# EPF-100_Logic.net
KiCad netlist of a schematic drawn in Altium Designer
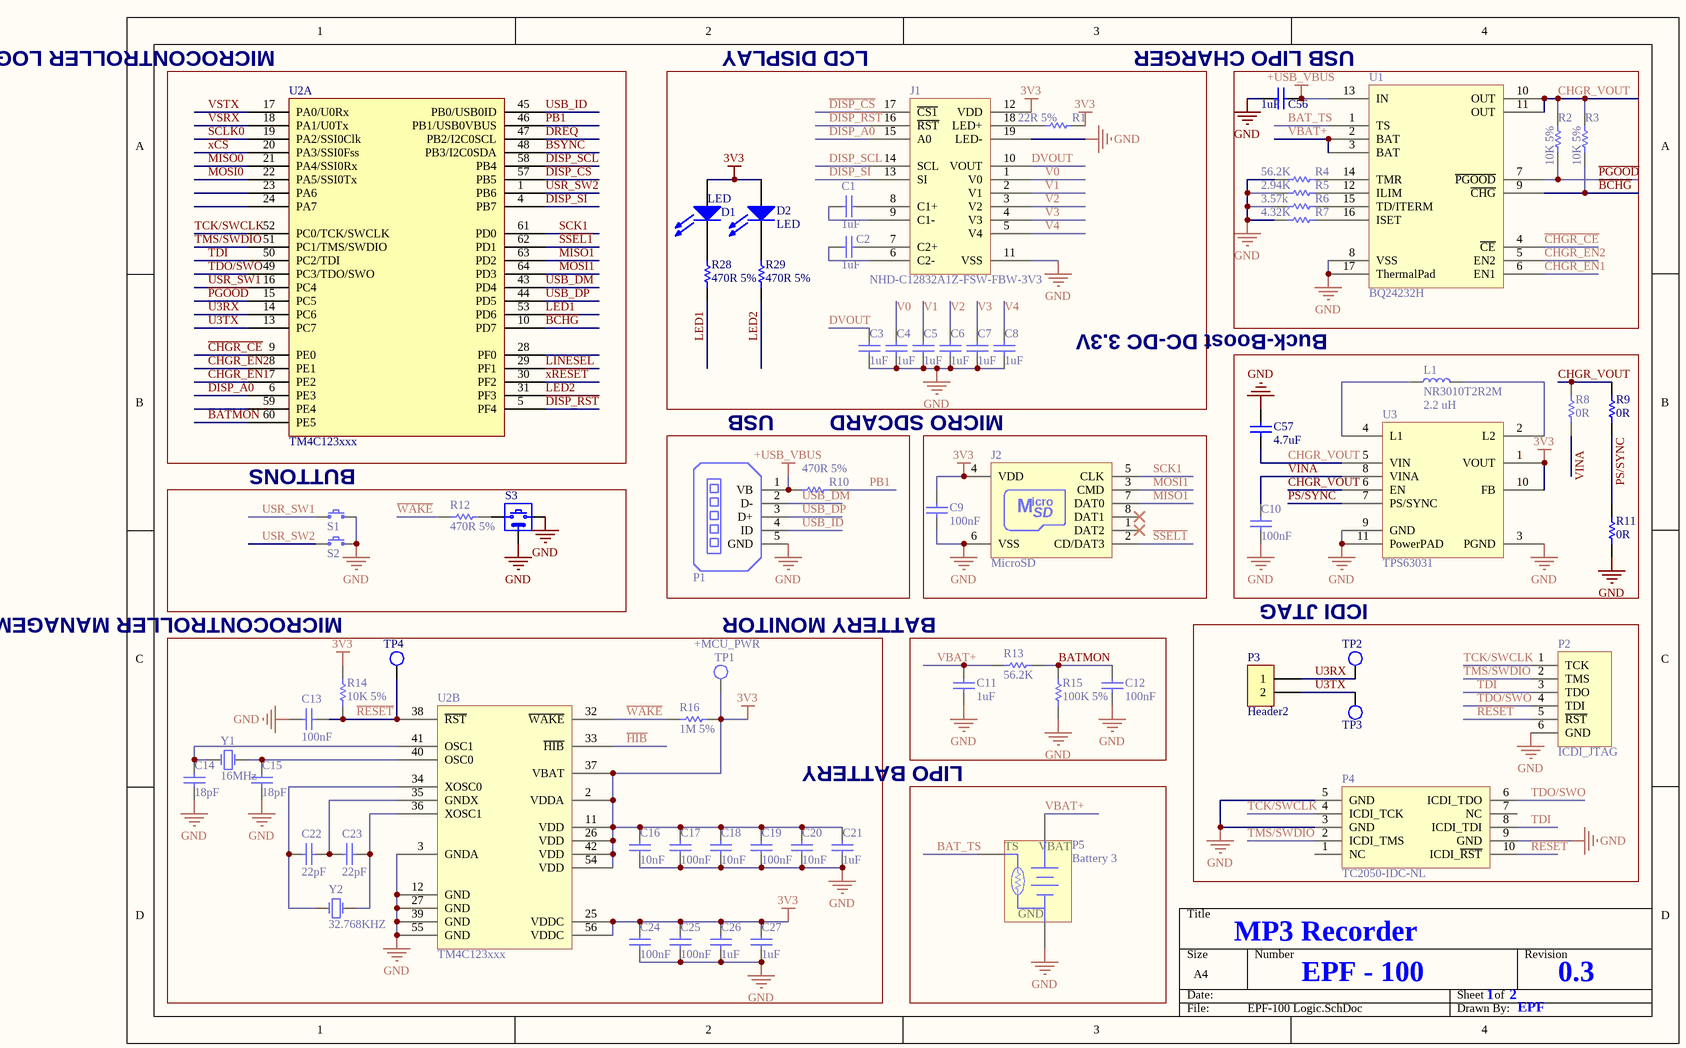
[diagram p0: EPF-100 Logic.SchDoc]

(export (version "E")
  (design (tool "Eeschema 10.0.6"))
  (components
    (comp (ref "C1")
      (value "1uF")
      (footprint "CAP0603")
      (description "X7R Ceramic Capacitors - SMD 0603")
      (fields (field (name "TOLERANCE") "X7R") (field (name "MANUFACTURER") "TDK"))
      (libsource (lib "Glober_Library") (part "CAP 1uF"))
    )
    (comp (ref "C2")
      (value "1uF")
      (footprint "CAP0603")
      (description "X7R Ceramic Capacitors - SMD 0603")
      (fields (field (name "TOLERANCE") "X7R") (field (name "MANUFACTURER") "TDK"))
      (libsource (lib "Glober_Library") (part "CAP 1uF"))
    )
    (comp (ref "C3")
      (value "1uF")
      (footprint "CAP0603")
      (description "X7R Ceramic Capacitors - SMD 0603")
      (fields (field (name "TOLERANCE") "X7R") (field (name "MANUFACTURER") "TDK"))
      (libsource (lib "Glober_Library") (part "CAP 1uF"))
    )
    (comp (ref "C4")
      (value "1uF")
      (footprint "CAP0603")
      (description "X7R Ceramic Capacitors - SMD 0603")
      (fields (field (name "TOLERANCE") "X7R") (field (name "MANUFACTURER") "TDK"))
      (libsource (lib "Glober_Library") (part "CAP 1uF"))
    )
    (comp (ref "C5")
      (value "1uF")
      (footprint "CAP0603")
      (description "X7R Ceramic Capacitors - SMD 0603")
      (fields (field (name "TOLERANCE") "X7R") (field (name "MANUFACTURER") "TDK"))
      (libsource (lib "Glober_Library") (part "CAP 1uF"))
    )
    (comp (ref "C6")
      (value "1uF")
      (footprint "CAP0603")
      (description "X7R Ceramic Capacitors - SMD 0603")
      (fields (field (name "TOLERANCE") "X7R") (field (name "MANUFACTURER") "TDK"))
      (libsource (lib "Glober_Library") (part "CAP 1uF"))
    )
    (comp (ref "C7")
      (value "1uF")
      (footprint "CAP0603")
      (description "X7R Ceramic Capacitors - SMD 0603")
      (fields (field (name "TOLERANCE") "X7R") (field (name "MANUFACTURER") "TDK"))
      (libsource (lib "Glober_Library") (part "CAP 1uF"))
    )
    (comp (ref "C8")
      (value "1uF")
      (footprint "CAP0603")
      (description "X7R Ceramic Capacitors - SMD 0603")
      (fields (field (name "TOLERANCE") "X7R") (field (name "MANUFACTURER") "TDK"))
      (libsource (lib "Glober_Library") (part "CAP 1uF"))
    )
    (comp (ref "C9")
      (value "100nF")
      (footprint "CAP0603")
      (description "X7R Ceramic Capacitors - SMD 0603")
      (fields (field (name "TOLERANCE") "X7R") (field (name "MANUFACTURER") "TDK"))
      (libsource (lib "GloberSchlib") (part "CAP 100nF"))
    )
    (comp (ref "C10")
      (value "100nF")
      (footprint "CAP0603")
      (description "X7R Ceramic Capacitors - SMD 0603")
      (fields (field (name "TOLERANCE") "X7R") (field (name "MANUFACTURER") "TDK"))
      (libsource (lib "Glober_Library") (part "CAP 100nF"))
    )
    (comp (ref "C11")
      (value "1uF")
      (footprint "CAP0603")
      (description "X7R Ceramic Capacitors - SMD 0603")
      (fields (field (name "TOLERANCE") "X7R") (field (name "MANUFACTURER") "TDK"))
      (libsource (lib "Glober_Library") (part "CAP 1uF"))
    )
    (comp (ref "C12")
      (value "100nF")
      (footprint "CAP0603")
      (description "X7R Ceramic Capacitors - SMD 0603")
      (fields (field (name "TOLERANCE") "X7R") (field (name "MANUFACTURER") "TDK"))
      (libsource (lib "Glober_Library") (part "CAP 100nF"))
    )
    (comp (ref "C13")
      (value "100nF")
      (footprint "CAP0603")
      (description "X7R Ceramic Capacitors - SMD 0603")
      (fields (field (name "TOLERANCE") "X7R") (field (name "MANUFACTURER") "TDK"))
      (libsource (lib "GloberSchlib") (part "CAP 100nF"))
    )
    (comp (ref "C14")
      (value "18pF")
      (footprint "CAP0603")
      (description "C0G Ceramic Capacitors - SMD 0603")
      (fields (field (name "TOLERANCE") "C0G") (field (name "MANUFACTURER") "Murata"))
      (libsource (lib "GloberSchlib") (part "CAP 18pF"))
    )
    (comp (ref "C15")
      (value "18pF")
      (footprint "CAP0603")
      (description "C0G Ceramic Capacitors - SMD 0603")
      (fields (field (name "TOLERANCE") "C0G") (field (name "MANUFACTURER") "Murata"))
      (libsource (lib "GloberSchlib") (part "CAP 18pF"))
    )
    (comp (ref "C16")
      (value "10nF")
      (footprint "CAP0603")
      (description "X7R Ceramic Capacitors - SMD 0603")
      (fields (field (name "TOLERANCE") "X7R") (field (name "MANUFACTURER") "TDK"))
      (libsource (lib "GloberSchlib") (part "CAP 10nF"))
    )
    (comp (ref "C17")
      (value "100nF")
      (footprint "CAP0603")
      (description "X7R Ceramic Capacitors - SMD 0603")
      (fields (field (name "TOLERANCE") "X7R") (field (name "MANUFACTURER") "TDK"))
      (libsource (lib "GloberSchlib") (part "CAP 100nF"))
    )
    (comp (ref "C18")
      (value "10nF")
      (footprint "CAP0603")
      (description "X7R Ceramic Capacitors - SMD 0603")
      (fields (field (name "TOLERANCE") "X7R") (field (name "MANUFACTURER") "TDK"))
      (libsource (lib "GloberSchlib") (part "CAP 10nF"))
    )
    (comp (ref "C19")
      (value "100nF")
      (footprint "CAP0603")
      (description "X7R Ceramic Capacitors - SMD 0603")
      (fields (field (name "TOLERANCE") "X7R") (field (name "MANUFACTURER") "TDK"))
      (libsource (lib "GloberSchlib") (part "CAP 100nF"))
    )
    (comp (ref "C20")
      (value "10nF")
      (footprint "CAP0603")
      (description "X7R Ceramic Capacitors - SMD 0603")
      (fields (field (name "TOLERANCE") "X7R") (field (name "MANUFACTURER") "TDK"))
      (libsource (lib "GloberSchlib") (part "CAP 10nF"))
    )
    (comp (ref "C21")
      (value "1uF")
      (footprint "CAP0603")
      (description "X7R Ceramic Capacitors - SMD 0603")
      (fields (field (name "TOLERANCE") "X7R") (field (name "MANUFACTURER") "TDK"))
      (libsource (lib "GloberSchlib") (part "CAP 1uF"))
    )
    (comp (ref "C22")
      (value "22pF")
      (footprint "CAP0603")
      (description "C0G Ceramic Capacitors - SMD 0603")
      (fields (field (name "TOLERANCE") "C0G") (field (name "MANUFACTURER") "TDK"))
      (libsource (lib "GloberSchlib") (part "CAP 22pF"))
    )
    (comp (ref "C23")
      (value "22pF")
      (footprint "CAP0603")
      (description "C0G Ceramic Capacitors - SMD 0603")
      (fields (field (name "TOLERANCE") "C0G") (field (name "MANUFACTURER") "TDK"))
      (libsource (lib "GloberSchlib") (part "CAP 22pF"))
    )
    (comp (ref "C24")
      (value "100nF")
      (footprint "CAP0603")
      (description "X7R Ceramic Capacitors - SMD 0603")
      (fields (field (name "TOLERANCE") "X7R") (field (name "MANUFACTURER") "TDK"))
      (libsource (lib "GloberSchlib") (part "CAP 100nF"))
    )
    (comp (ref "C25")
      (value "100nF")
      (footprint "CAP0603")
      (description "X7R Ceramic Capacitors - SMD 0603")
      (fields (field (name "TOLERANCE") "X7R") (field (name "MANUFACTURER") "TDK"))
      (libsource (lib "GloberSchlib") (part "CAP 100nF"))
    )
    (comp (ref "C26")
      (value "1uF")
      (footprint "CAP0603")
      (description "X7R Ceramic Capacitors - SMD 0603")
      (fields (field (name "TOLERANCE") "X7R") (field (name "MANUFACTURER") "TDK"))
      (libsource (lib "GloberSchlib") (part "CAP 1uF"))
    )
    (comp (ref "C27")
      (value "1uF")
      (footprint "CAP0603")
      (description "X7R Ceramic Capacitors - SMD 0603")
      (fields (field (name "TOLERANCE") "X7R") (field (name "MANUFACTURER") "TDK"))
      (libsource (lib "GloberSchlib") (part "CAP 1uF"))
    )
    (comp (ref "C56")
      (value "1uF")
      (footprint "CAP0603")
      (description "X7R Ceramic Capacitors - SMD 0603")
      (fields (field (name "TOLERANCE") "X7R") (field (name "MANUFACTURER") "TDK"))
      (libsource (lib "Glober_Library") (part "CAP 1uF"))
    )
    (comp (ref "C57")
      (value "4.7uF")
      (footprint "CAP0603")
      (description "X7R Ceramic Capacitors - SMD 0603")
      (fields (field (name "TOLERANCE") "X7R") (field (name "MANUFACTURER") "Murata Electronics"))
      (libsource (lib "Glober_Library") (part "CAP 4.7uF"))
    )
    (comp (ref "D1") (value "LED") (footprint "LED0603") (libsource (lib "epf") (part "LED1")))
    (comp (ref "D2") (value "LED") (footprint "LED0603") (libsource (lib "epf") (part "LED1")))
    (comp (ref "J1")
      (value "NHD-C12832A1Z-FSW-FBW-3V3")
      (footprint "NHD-C12832A1Z")
      (description "LCD NHD-C12832A1Z-FSW-FBW-3V3")
      (libsource (lib "Glober_Library") (part "NHD-C12832A1Z-FSW-FBW-3V3"))
    )
    (comp (ref "J2")
      (value "MicroSD")
      (footprint "ALPS-SCHD1A0101")
      (description "MicroSD Memory Card Connector")
      (fields (field (name "MANUFACTURER") "ALPS"))
      (libsource (lib "GloberSchlib") (part "ALPS-SCHD1A0101"))
    )
    (comp (ref "L1")
      (value "NR3010T2R2M")
      (footprint "NR3010")
      (fields
        (field (name "MANUFACTURER") "Taiyo Yuden")
        (field (name "MOUSER PART #") "963-NR3010T2R2M")
        (field (name "ALTIUM_VALUE") "2.2 uH")
      )
      (libsource (lib "Glober_Library") (part "NR3010T2R2M"))
    )
    (comp (ref "P1")
      (value "USB extension")
      (footprint "HDR1X5 - USB")
      (libsource (lib "GloberSchlib") (part "USB"))
    )
    (comp (ref "P2")
      (value "ICDI_JTAG")
      (footprint "HDR1X6")
      (description "DEBUG ICDI_JTAG")
      (libsource (lib "Glober_Library") (part "ICDI_JTAG"))
    )
    (comp (ref "P3") (value "Header2") (footprint "Header2Macho") (libsource (lib "epf") (part "Header2")))
    (comp (ref "P4")
      (value "TC2050-IDC-NL")
      (footprint "TC2050-IDC-NL")
      (fields (field (name "MANUFACTURER") "Tag-Connect LLC"))
      (libsource (lib "GloberSchlib") (part "TC2050-IDC-NL"))
    )
    (comp (ref "P5")
      (value "Battery 3")
      (footprint "HDR1X3")
      (description "Header, 3-Pin")
      (fields (field (name "PUBLISHER") "Altium Limited"))
      (libsource (lib "GloberSchlib") (part "Battery 3"))
    )
    (comp (ref "R1")
      (value "22R 5%")
      (footprint "RES0603")
      (description "5% Thick Film Resistors - SMD 0603")
      (fields (field (name "TOLERANCE") "5%") (field (name "MANUFACTURER") "Bourns"))
      (libsource (lib "Glober_Library") (part "RES 22R"))
    )
    (comp (ref "R2")
      (value "10K 5%")
      (footprint "RES0603")
      (description "5% Thick Film Resistors - SMD 0603")
      (fields (field (name "TOLERANCE") "5%") (field (name "MANUFACTURER") "Bourns"))
      (libsource (lib "Glober_Library") (part "RES 10K"))
    )
    (comp (ref "R3")
      (value "10K 5%")
      (footprint "RES0603")
      (description "5% Thick Film Resistors - SMD 0603")
      (fields (field (name "TOLERANCE") "5%") (field (name "MANUFACTURER") "Bourns"))
      (libsource (lib "Glober_Library") (part "RES 10K"))
    )
    (comp (ref "R4")
      (value "56.2K")
      (footprint "RES0603")
      (description "1% Thick Film Resistors - SMD 0603")
      (fields (field (name "TOLERANCE") "5%") (field (name "MANUFACTURER") "Panasonic"))
      (libsource (lib "Glober_Library") (part "RES 56.2K"))
    )
    (comp (ref "R5")
      (value "2.94K")
      (footprint "RES0603")
      (description "1% Thick Film Resistors - SMD 0603")
      (fields (field (name "TOLERANCE") "1%") (field (name "MANUFACTURER") "Vishay / Dale"))
      (libsource (lib "Glober_Library") (part "RES 2.94K"))
    )
    (comp (ref "R6")
      (value "3.57k")
      (footprint "RES0603")
      (description "1% Thick Film Resistors - SMD 0603")
      (fields (field (name "TOLERANCE") "1%") (field (name "MANUFACTURER") "Panasonic"))
      (libsource (lib "Glober_Library") (part "RES 3.57k"))
    )
    (comp (ref "R7")
      (value "4.32K")
      (footprint "RES0603")
      (description "1% Thick Film Resistors - SMD 0603")
      (fields (field (name "TOLERANCE") "1%") (field (name "MANUFACTURER") "Panasonic"))
      (libsource (lib "Glober_Library") (part "RES 4.32K"))
    )
    (comp (ref "R8")
      (value "0R")
      (footprint "RES0603")
      (description "5% Thick Film Resistors - SMD 0603")
      (fields (field (name "TOLERANCE") "5%") (field (name "MANUFACTURER") "KOA Speer"))
      (libsource (lib "Glober_Library") (part "RES 0R"))
    )
    (comp (ref "R9")
      (value "0R")
      (footprint "RES0603")
      (description "5% Thick Film Resistors - SMD 0603")
      (fields (field (name "TOLERANCE") "5%") (field (name "MANUFACTURER") "KOA Speer"))
      (libsource (lib "Glober_Library") (part "RES 0R"))
    )
    (comp (ref "R10")
      (value "470R 5%")
      (footprint "RES0603")
      (description "5% Thick Film Resistors - SMD 0603")
      (fields (field (name "TOLERANCE") "5%") (field (name "MANUFACTURER") "Bourns"))
      (libsource (lib "Glober_Library") (part "RES 470R"))
    )
    (comp (ref "R11")
      (value "0R")
      (footprint "RES0603")
      (description "5% Thick Film Resistors - SMD 0603")
      (fields (field (name "TOLERANCE") "5%") (field (name "MANUFACTURER") "KOA Speer"))
      (libsource (lib "Glober_Library") (part "RES 0R"))
    )
    (comp (ref "R12")
      (value "470R 5%")
      (footprint "RES0603")
      (description "5% Thick Film Resistors - SMD 0603")
      (fields (field (name "TOLERANCE") "5%") (field (name "MANUFACTURER") "Bourns"))
      (libsource (lib "Glober_Library") (part "RES 470R"))
    )
    (comp (ref "R13")
      (value "56.2K")
      (footprint "RES0603")
      (description "1% Thick Film Resistors - SMD 0603")
      (fields (field (name "TOLERANCE") "5%") (field (name "MANUFACTURER") "Panasonic"))
      (libsource (lib "Glober_Library") (part "RES 56.2K"))
    )
    (comp (ref "R14")
      (value "10K 5%")
      (footprint "RES0603")
      (description "5% Thick Film Resistors - SMD 0603")
      (fields (field (name "TOLERANCE") "5%") (field (name "MANUFACTURER") "Bourns"))
      (libsource (lib "Glober_Library") (part "RES 10K"))
    )
    (comp (ref "R15")
      (value "100K 5%")
      (footprint "RES0603")
      (description "5% Thick Film Resistors - SMD 0603")
      (fields (field (name "TOLERANCE") "5%") (field (name "MANUFACTURER") "Bourns"))
      (libsource (lib "Glober_Library") (part "RES 100K"))
    )
    (comp (ref "R16")
      (value "1M 5%")
      (footprint "RES0603")
      (description "5% Thick Film Resistors - SMD 0603")
      (fields (field (name "TOLERANCE") "5%") (field (name "MANUFACTURER") "Bourns"))
      (libsource (lib "Glober_Library") (part "RES 1M"))
    )
    (comp (ref "R28")
      (value "470R 5%")
      (footprint "RES0603")
      (description "5% Thick Film Resistors - SMD 0603")
      (fields (field (name "TOLERANCE") "5%") (field (name "MANUFACTURER") "Bourns"))
      (libsource (lib "Glober_Library") (part "RES 470R"))
    )
    (comp (ref "R29")
      (value "470R 5%")
      (footprint "RES0603")
      (description "5% Thick Film Resistors - SMD 0603")
      (fields (field (name "TOLERANCE") "5%") (field (name "MANUFACTURER") "Bourns"))
      (libsource (lib "Glober_Library") (part "RES 470R"))
    )
    (comp (ref "S1")
      (value "switch")
      (footprint "TACTILE SWITCH 3.5x6")
      (description "TACTILE SWITCH 3.5x6")
      (libsource (lib "Glober_Library") (part "SW-PB"))
    )
    (comp (ref "S2")
      (value "switch")
      (footprint "TACTILE SWITCH 3.5x6")
      (description "TACTILE SWITCH 3.5x6")
      (libsource (lib "Glober_Library") (part "SW-PB"))
    )
    (comp (ref "S3")
      (value "switch")
      (footprint "B3U-3100P-B")
      (description "B3U-3100P-B")
      (fields (field (name "MANUFACTURER") "Omron"))
      (libsource (lib "Glober_Library") (part "B3U-3100P-B"))
    )
    (comp (ref "TP1")
      (value "+MCU_PWR")
      (footprint "PCB TEST POINT")
      (libsource (lib "Glober_Library") (part "PCB TEST POINT"))
    )
    (comp (ref "TP2")
      (value "PCB TEST POINT")
      (footprint "PCB TEST POINT")
      (libsource (lib "Glober_Library") (part "PCB TEST POINT"))
    )
    (comp (ref "TP3")
      (value "PCB TEST POINT")
      (footprint "PCB TEST POINT")
      (libsource (lib "Glober_Library") (part "PCB TEST POINT"))
    )
    (comp (ref "TP4")
      (value "PCB TEST POINT")
      (footprint "PCB TEST POINT")
      (libsource (lib "Glober_Library") (part "PCB TEST POINT"))
    )
    (comp (ref "U1")
      (value "BQ24232H")
      (footprint "QFN50P300X300-16V6N")
      (description "USB-Friendly Lithium-Ion Battery Charger and Power-Path Management IC")
      (fields (field (name "MANUFACTURER") "Ti"))
      (libsource (lib "Glober_Library") (part "BQ24232H"))
    )
    (comp (ref "U2")
      (value "TM4C123xxx")
      (footprint "LQFP64_N")
      (fields (field (name "MANUFACTURER") "Ti"))
      (libsource (lib "Glober_Library") (part "TM4C123"))
    )
    (comp (ref "U3")
      (value "TPS63031")
      (footprint "SON50P300X300X80-10W2N")
      (description "HIGH EFFICIENCY SINGLE INDUCTOR BUCK-BOOST CONVERTER WITH 1-A SWITCHES")
      (fields (field (name "MANUFACTURER") "Ti"))
      (libsource (lib "Glober_Library") (part "TPS63031"))
    )
    (comp (ref "Y1")
      (value "16MHz")
      (footprint "NX5032GA")
      (description "Crystal, 16.00 MHz 5.0x3.2mm SMT")
      (fields (field (name "MANUFACTURER") "NDK"))
      (libsource (lib "GloberSchlib") (part "XTAL 16MHz"))
    )
    (comp (ref "Y2")
      (value "32.768KHZ")
      (footprint "AB26TRB-32.768KHZ- T")
      (description "Crystal, 32.768 kHz Radial Can")
      (fields (field (name "MANUFACTURER") "Abracon"))
      (libsource (lib "GloberSchlib") (part "XTAL 32.768KHZ"))
    )
  )
  (nets
    (net (code "1") (name "+USB_VBUS") (class "Default")
      (node (ref "C56") (pin "1") (pinfunction "1_1") (pintype "passive"))
      (node (ref "P1") (pin "1") (pinfunction "VB_1") (pintype "passive"))
      (node (ref "R10") (pin "1") (pinfunction "1_1") (pintype "passive"))
      (node (ref "U1") (pin "13") (pinfunction "IN_13") (pintype "passive"))
    )
    (net (code "2") (name "/BATMON") (class "Default")
      (node (ref "C12") (pin "2") (pinfunction "2_2") (pintype "passive"))
      (node (ref "R13") (pin "2") (pinfunction "2_2") (pintype "passive"))
      (node (ref "R15") (pin "2") (pinfunction "2_2") (pintype "passive"))
      (node (ref "U2") (pin "60") (pinfunction "PE5_60") (pintype "passive"))
    )
    (net (code "3") (name "/BAT_TS") (class "Default")
      (node (ref "P5") (pin "1") (pinfunction "TS_1") (pintype "passive"))
      (node (ref "U1") (pin "1") (pinfunction "TS_1") (pintype "passive"))
    )
    (net (code "4") (name "/BSYNC") (class "Default")
      (node (ref "U2") (pin "48") (pinfunction "PB3/I2C0SDA_48") (pintype "passive"))
    )
    (net (code "5") (name "/CHGR_EN1") (class "Default")
      (node (ref "U1") (pin "6") (pinfunction "EN1_6") (pintype "passive"))
      (node (ref "U2") (pin "7") (pinfunction "PE2_7") (pintype "passive"))
    )
    (net (code "6") (name "/CHGR_EN2") (class "Default")
      (node (ref "U1") (pin "5") (pinfunction "EN2_5") (pintype "passive"))
      (node (ref "U2") (pin "8") (pinfunction "PE1_8") (pintype "passive"))
    )
    (net (code "7") (name "/CHGR_VOUT") (class "Default")
      (node (ref "C57") (pin "1") (pinfunction "1_1") (pintype "passive"))
      (node (ref "R2") (pin "2") (pinfunction "2_2") (pintype "passive"))
      (node (ref "R3") (pin "2") (pinfunction "2_2") (pintype "passive"))
      (node (ref "R8") (pin "1") (pinfunction "1_1") (pintype "passive"))
      (node (ref "R9") (pin "1") (pinfunction "1_1") (pintype "passive"))
      (node (ref "U1") (pin "10") (pinfunction "OUT_10") (pintype "passive"))
      (node (ref "U1") (pin "11") (pinfunction "OUT_11") (pintype "passive"))
      (node (ref "U3") (pin "5") (pinfunction "VIN_5") (pintype "passive"))
      (node (ref "U3") (pin "6") (pinfunction "EN_6") (pintype "passive"))
    )
    (net (code "8") (name "/DISP_A0") (class "Default")
      (node (ref "J1") (pin "15") (pinfunction "A0_15") (pintype "passive"))
      (node (ref "U2") (pin "6") (pinfunction "PE3_6") (pintype "passive"))
    )
    (net (code "9") (name "/DISP_SCL") (class "Default")
      (node (ref "J1") (pin "14") (pinfunction "SCL_14") (pintype "passive"))
      (node (ref "U2") (pin "58") (pinfunction "PB4_58") (pintype "passive"))
    )
    (net (code "10") (name "/DISP_SI") (class "Default")
      (node (ref "J1") (pin "13") (pinfunction "SI_13") (pintype "passive"))
      (node (ref "U2") (pin "4") (pinfunction "PB7_4") (pintype "passive"))
    )
    (net (code "11") (name "/DREQ") (class "Default")
      (node (ref "U2") (pin "47") (pinfunction "PB2/I2C0SCL_47") (pintype "passive"))
    )
    (net (code "12") (name "/DVOUT") (class "Default")
      (node (ref "C3") (pin "1") (pinfunction "1_1") (pintype "passive"))
      (node (ref "J1") (pin "10") (pinfunction "VOUT_10") (pintype "passive"))
    )
    (net (code "13") (name "/LED1") (class "Default")
      (node (ref "R28") (pin "1") (pinfunction "1_1") (pintype "passive"))
      (node (ref "U2") (pin "53") (pinfunction "PD6_53") (pintype "passive"))
    )
    (net (code "14") (name "/LED2") (class "Default")
      (node (ref "R29") (pin "1") (pinfunction "1_1") (pintype "passive"))
      (node (ref "U2") (pin "31") (pinfunction "PF3_31") (pintype "passive"))
    )
    (net (code "15") (name "/LINESEL") (class "Default")
      (node (ref "U2") (pin "29") (pinfunction "PF1_29") (pintype "passive"))
    )
    (net (code "16") (name "/MISO0") (class "Default")
      (node (ref "U2") (pin "21") (pinfunction "PA4/SSI0Rx_21") (pintype "passive"))
    )
    (net (code "17") (name "/MISO1") (class "Default")
      (node (ref "J2") (pin "7") (pinfunction "DAT0_7") (pintype "passive"))
      (node (ref "U2") (pin "63") (pinfunction "PD2_63") (pintype "passive"))
    )
    (net (code "18") (name "/MOSI0") (class "Default")
      (node (ref "U2") (pin "22") (pinfunction "PA5/SSI0Tx_22") (pintype "passive"))
    )
    (net (code "19") (name "/MOSI1") (class "Default")
      (node (ref "J2") (pin "3") (pinfunction "CMD_3") (pintype "passive"))
      (node (ref "U2") (pin "64") (pinfunction "PD3_64") (pintype "passive"))
    )
    (net (code "20") (name "/PB1") (class "Default")
      (node (ref "R10") (pin "2") (pinfunction "2_2") (pintype "passive"))
      (node (ref "U2") (pin "46") (pinfunction "PB1/USB0VBUS_46") (pintype "passive"))
    )
    (net (code "21") (name "/PS{slash}SYNC") (class "Default")
      (node (ref "R11") (pin "2") (pinfunction "2_2") (pintype "passive"))
      (node (ref "R9") (pin "2") (pinfunction "2_2") (pintype "passive"))
      (node (ref "U3") (pin "7") (pinfunction "PS/SYNC_7") (pintype "passive"))
    )
    (net (code "22") (name "/SCK1") (class "Default")
      (node (ref "J2") (pin "5") (pinfunction "CLK_5") (pintype "passive"))
      (node (ref "U2") (pin "61") (pinfunction "PD0_61") (pintype "passive"))
    )
    (net (code "23") (name "/SCLK0") (class "Default")
      (node (ref "U2") (pin "19") (pinfunction "PA2/SSI0Clk_19") (pintype "passive"))
    )
    (net (code "24") (name "/SSEL1") (class "Default")
      (node (ref "J2") (pin "2") (pinfunction "CD/DAT3_2") (pintype "passive"))
      (node (ref "U2") (pin "62") (pinfunction "PD1_62") (pintype "passive"))
    )
    (net (code "25") (name "/TCK{slash}SWCLK") (class "Default")
      (node (ref "P2") (pin "1") (pinfunction "TCK_1") (pintype "passive"))
      (node (ref "P4") (pin "4") (pinfunction "ICDI_TCK_4") (pintype "passive"))
      (node (ref "U2") (pin "52") (pinfunction "PC0/TCK/SWCLK_52") (pintype "passive"))
    )
    (net (code "26") (name "/TDI") (class "Default")
      (node (ref "P2") (pin "3") (pinfunction "TDO_3") (pintype "passive"))
      (node (ref "P4") (pin "8") (pinfunction "ICDI_TDI_8") (pintype "passive"))
      (node (ref "U2") (pin "50") (pinfunction "PC2/TDI_50") (pintype "passive"))
    )
    (net (code "27") (name "/TDO{slash}SWO") (class "Default")
      (node (ref "P2") (pin "4") (pinfunction "TDI_4") (pintype "passive"))
      (node (ref "P4") (pin "6") (pinfunction "ICDI_TDO_6") (pintype "passive"))
      (node (ref "U2") (pin "49") (pinfunction "PC3/TDO/SWO_49") (pintype "passive"))
    )
    (net (code "28") (name "/TMS{slash}SWDIO") (class "Default")
      (node (ref "P2") (pin "2") (pinfunction "TMS_2") (pintype "passive"))
      (node (ref "P4") (pin "2") (pinfunction "ICDI_TMS_2") (pintype "passive"))
      (node (ref "U2") (pin "51") (pinfunction "PC1/TMS/SWDIO_51") (pintype "passive"))
    )
    (net (code "29") (name "/U3RX") (class "Default")
      (node (ref "P3") (pin "1") (pinfunction "1_1") (pintype "passive"))
      (node (ref "TP2") (pin "1") (pinfunction "1_1") (pintype "passive"))
      (node (ref "U2") (pin "14") (pinfunction "PC6_14") (pintype "passive"))
    )
    (net (code "30") (name "/U3TX") (class "Default")
      (node (ref "P3") (pin "2") (pinfunction "2_2") (pintype "passive"))
      (node (ref "TP3") (pin "1") (pinfunction "1_1") (pintype "passive"))
      (node (ref "U2") (pin "13") (pinfunction "PC7_13") (pintype "passive"))
    )
    (net (code "31") (name "/USB_DM") (class "Default")
      (node (ref "P1") (pin "2") (pinfunction "D-_2") (pintype "passive"))
      (node (ref "U2") (pin "43") (pinfunction "PD4_43") (pintype "passive"))
    )
    (net (code "32") (name "/USB_DP") (class "Default")
      (node (ref "P1") (pin "3") (pinfunction "D+_3") (pintype "passive"))
      (node (ref "U2") (pin "44") (pinfunction "PD5_44") (pintype "passive"))
    )
    (net (code "33") (name "/USB_ID") (class "Default")
      (node (ref "P1") (pin "4") (pinfunction "ID_4") (pintype "passive"))
      (node (ref "U2") (pin "45") (pinfunction "PB0/USB0ID_45") (pintype "passive"))
    )
    (net (code "34") (name "/USR_SW1") (class "Default")
      (node (ref "S1") (pin "1") (pinfunction "0_1") (pintype "passive"))
      (node (ref "U2") (pin "16") (pinfunction "PC4_16") (pintype "passive"))
    )
    (net (code "35") (name "/USR_SW2") (class "Default")
      (node (ref "S2") (pin "1") (pinfunction "0_1") (pintype "passive"))
      (node (ref "U2") (pin "1") (pinfunction "PB6_1") (pintype "passive"))
    )
    (net (code "36") (name "/V0") (class "Default")
      (node (ref "C4") (pin "1") (pinfunction "1_1") (pintype "passive"))
      (node (ref "J1") (pin "1") (pinfunction "V0_1") (pintype "passive"))
    )
    (net (code "37") (name "/V1") (class "Default")
      (node (ref "C5") (pin "1") (pinfunction "1_1") (pintype "passive"))
      (node (ref "J1") (pin "2") (pinfunction "V1_2") (pintype "passive"))
    )
    (net (code "38") (name "/V2") (class "Default")
      (node (ref "C6") (pin "1") (pinfunction "1_1") (pintype "passive"))
      (node (ref "J1") (pin "3") (pinfunction "V2_3") (pintype "passive"))
    )
    (net (code "39") (name "/V3") (class "Default")
      (node (ref "C7") (pin "1") (pinfunction "1_1") (pintype "passive"))
      (node (ref "J1") (pin "4") (pinfunction "V3_4") (pintype "passive"))
    )
    (net (code "40") (name "/V4") (class "Default")
      (node (ref "C8") (pin "1") (pinfunction "1_1") (pintype "passive"))
      (node (ref "J1") (pin "5") (pinfunction "V4_5") (pintype "passive"))
    )
    (net (code "41") (name "/VBAT+") (class "Default")
      (node (ref "C11") (pin "2") (pinfunction "2_2") (pintype "passive"))
      (node (ref "P5") (pin "2") (pinfunction "VBAT_2") (pintype "passive"))
      (node (ref "R13") (pin "1") (pinfunction "1_1") (pintype "passive"))
      (node (ref "U1") (pin "2") (pinfunction "BAT_2") (pintype "passive"))
      (node (ref "U1") (pin "3") (pinfunction "BAT_3") (pintype "passive"))
    )
    (net (code "42") (name "/VINA") (class "Default")
      (node (ref "C10") (pin "2") (pinfunction "2_2") (pintype "passive"))
      (node (ref "R8") (pin "2") (pinfunction "2_2") (pintype "passive"))
      (node (ref "U3") (pin "8") (pinfunction "VINA_8") (pintype "passive"))
    )
    (net (code "43") (name "/VSRX") (class "Default")
      (node (ref "U2") (pin "18") (pinfunction "PA1/U0Tx_18") (pintype "passive"))
    )
    (net (code "44") (name "/VSTX") (class "Default")
      (node (ref "U2") (pin "17") (pinfunction "PA0/U0Rx_17") (pintype "passive"))
    )
    (net (code "45") (name "/~{BCHG}") (class "Default")
      (node (ref "R3") (pin "1") (pinfunction "1_1") (pintype "passive"))
      (node (ref "U1") (pin "9") (pinfunction "~{CHG}_9") (pintype "passive"))
      (node (ref "U2") (pin "10") (pinfunction "PD7_10") (pintype "passive"))
    )
    (net (code "46") (name "/~{CHGR_CE}") (class "Default")
      (node (ref "U1") (pin "4") (pinfunction "~{CE}_4") (pintype "passive"))
      (node (ref "U2") (pin "9") (pinfunction "PE0_9") (pintype "passive"))
    )
    (net (code "47") (name "/~{DISP_CS}") (class "Default")
      (node (ref "J1") (pin "17") (pinfunction "~{CS1}_17") (pintype "passive"))
      (node (ref "U2") (pin "57") (pinfunction "PB5_57") (pintype "passive"))
    )
    (net (code "48") (name "/~{DISP_RST}") (class "Default")
      (node (ref "J1") (pin "16") (pinfunction "~{RST}_16") (pintype "passive"))
      (node (ref "U2") (pin "5") (pinfunction "PF4_5") (pintype "passive"))
    )
    (net (code "49") (name "/~{HIB}") (class "Default")
      (node (ref "U2") (pin "33") (pinfunction "~{HIB}_33") (pintype "passive"))
    )
    (net (code "50") (name "/~{PGOOD}") (class "Default")
      (node (ref "R2") (pin "1") (pinfunction "1_1") (pintype "passive"))
      (node (ref "U1") (pin "7") (pinfunction "~{PGOOD}_7") (pintype "passive"))
      (node (ref "U2") (pin "15") (pinfunction "PC5_15") (pintype "passive"))
    )
    (net (code "51") (name "/~{RESET}") (class "Default")
      (node (ref "C13") (pin "2") (pinfunction "2_2") (pintype "passive"))
      (node (ref "P2") (pin "5") (pinfunction "~{RST}_5") (pintype "passive"))
      (node (ref "P4") (pin "10") (pinfunction "ICDI_~{RST}_10") (pintype "passive"))
      (node (ref "R14") (pin "1") (pinfunction "1_1") (pintype "passive"))
      (node (ref "TP4") (pin "1") (pinfunction "1_1") (pintype "passive"))
      (node (ref "U2") (pin "38") (pinfunction "~{RST}_38") (pintype "passive"))
    )
    (net (code "52") (name "/~{WAKE}") (class "Default")
      (node (ref "R12") (pin "1") (pinfunction "1_1") (pintype "passive"))
      (node (ref "R16") (pin "1") (pinfunction "1_1") (pintype "passive"))
      (node (ref "U2") (pin "32") (pinfunction "~{WAKE}_32") (pintype "passive"))
    )
    (net (code "53") (name "/~{xCS}") (class "Default")
      (node (ref "U2") (pin "20") (pinfunction "PA3/SSI0Fss_20") (pintype "passive"))
    )
    (net (code "54") (name "/~{xRESET}") (class "Default")
      (node (ref "U2") (pin "30") (pinfunction "PF2_30") (pintype "passive"))
    )
    (net (code "55") (name "3V3") (class "Default")
      (node (ref "C16") (pin "2") (pinfunction "2_2") (pintype "passive"))
      (node (ref "C17") (pin "2") (pinfunction "2_2") (pintype "passive"))
      (node (ref "C18") (pin "2") (pinfunction "2_2") (pintype "passive"))
      (node (ref "C19") (pin "2") (pinfunction "2_2") (pintype "passive"))
      (node (ref "C20") (pin "2") (pinfunction "2_2") (pintype "passive"))
      (node (ref "C21") (pin "2") (pinfunction "2_2") (pintype "passive"))
      (node (ref "C24") (pin "2") (pinfunction "2_2") (pintype "passive"))
      (node (ref "C25") (pin "2") (pinfunction "2_2") (pintype "passive"))
      (node (ref "C26") (pin "2") (pinfunction "2_2") (pintype "passive"))
      (node (ref "C27") (pin "2") (pinfunction "2_2") (pintype "passive"))
      (node (ref "C9") (pin "2") (pinfunction "2_2") (pintype "passive"))
      (node (ref "D1") (pin "1") (pinfunction "A_1") (pintype "passive"))
      (node (ref "D2") (pin "1") (pinfunction "A_1") (pintype "passive"))
      (node (ref "J1") (pin "12") (pinfunction "VDD_12") (pintype "passive"))
      (node (ref "J2") (pin "4") (pinfunction "VDD_4") (pintype "power_in"))
      (node (ref "R1") (pin "1") (pinfunction "1_1") (pintype "passive"))
      (node (ref "R14") (pin "2") (pinfunction "2_2") (pintype "passive"))
      (node (ref "R16") (pin "2") (pinfunction "2_2") (pintype "passive"))
      (node (ref "TP1") (pin "1") (pinfunction "1_1") (pintype "passive"))
      (node (ref "U2") (pin "11") (pinfunction "VDD_11") (pintype "passive"))
      (node (ref "U2") (pin "2") (pinfunction "VDDA_2") (pintype "passive"))
      (node (ref "U2") (pin "25") (pinfunction "VDDC_25") (pintype "passive"))
      (node (ref "U2") (pin "26") (pinfunction "VDD_26") (pintype "passive"))
      (node (ref "U2") (pin "37") (pinfunction "VBAT_37") (pintype "passive"))
      (node (ref "U2") (pin "42") (pinfunction "VDD_42") (pintype "passive"))
      (node (ref "U2") (pin "54") (pinfunction "VDD_54") (pintype "passive"))
      (node (ref "U2") (pin "56") (pinfunction "VDDC_56") (pintype "passive"))
      (node (ref "U3") (pin "1") (pinfunction "VOUT_1") (pintype "passive"))
      (node (ref "U3") (pin "10") (pinfunction "FB_10") (pintype "passive"))
    )
    (net (code "56") (name "GND") (class "Default")
      (node (ref "C10") (pin "1") (pinfunction "1_1") (pintype "passive"))
      (node (ref "C11") (pin "1") (pinfunction "1_1") (pintype "passive"))
      (node (ref "C12") (pin "1") (pinfunction "1_1") (pintype "passive"))
      (node (ref "C13") (pin "1") (pinfunction "1_1") (pintype "passive"))
      (node (ref "C14") (pin "2") (pinfunction "2_2") (pintype "passive"))
      (node (ref "C15") (pin "2") (pinfunction "2_2") (pintype "passive"))
      (node (ref "C16") (pin "1") (pinfunction "1_1") (pintype "passive"))
      (node (ref "C17") (pin "1") (pinfunction "1_1") (pintype "passive"))
      (node (ref "C18") (pin "1") (pinfunction "1_1") (pintype "passive"))
      (node (ref "C19") (pin "1") (pinfunction "1_1") (pintype "passive"))
      (node (ref "C20") (pin "1") (pinfunction "1_1") (pintype "passive"))
      (node (ref "C21") (pin "1") (pinfunction "1_1") (pintype "passive"))
      (node (ref "C24") (pin "1") (pinfunction "1_1") (pintype "passive"))
      (node (ref "C25") (pin "1") (pinfunction "1_1") (pintype "passive"))
      (node (ref "C26") (pin "1") (pinfunction "1_1") (pintype "passive"))
      (node (ref "C27") (pin "1") (pinfunction "1_1") (pintype "passive"))
      (node (ref "C3") (pin "2") (pinfunction "2_2") (pintype "passive"))
      (node (ref "C4") (pin "2") (pinfunction "2_2") (pintype "passive"))
      (node (ref "C5") (pin "2") (pinfunction "2_2") (pintype "passive"))
      (node (ref "C56") (pin "2") (pinfunction "2_2") (pintype "passive"))
      (node (ref "C57") (pin "2") (pinfunction "2_2") (pintype "passive"))
      (node (ref "C6") (pin "2") (pinfunction "2_2") (pintype "passive"))
      (node (ref "C7") (pin "2") (pinfunction "2_2") (pintype "passive"))
      (node (ref "C8") (pin "2") (pinfunction "2_2") (pintype "passive"))
      (node (ref "C9") (pin "1") (pinfunction "1_1") (pintype "passive"))
      (node (ref "J1") (pin "11") (pinfunction "VSS_11") (pintype "passive"))
      (node (ref "J1") (pin "19") (pinfunction "LED-_19") (pintype "passive"))
      (node (ref "J2") (pin "6") (pinfunction "VSS_6") (pintype "power_in"))
      (node (ref "P1") (pin "5") (pinfunction "GND_5") (pintype "passive"))
      (node (ref "P2") (pin "6") (pinfunction "GND_6") (pintype "passive"))
      (node (ref "P4") (pin "3") (pinfunction "GND_3") (pintype "passive"))
      (node (ref "P4") (pin "5") (pinfunction "GND_5") (pintype "passive"))
      (node (ref "P4") (pin "9") (pinfunction "GND_9") (pintype "passive"))
      (node (ref "P5") (pin "3") (pinfunction "GND_3") (pintype "passive"))
      (node (ref "R11") (pin "1") (pinfunction "1_1") (pintype "passive"))
      (node (ref "R15") (pin "1") (pinfunction "1_1") (pintype "passive"))
      (node (ref "R4") (pin "1") (pinfunction "1_1") (pintype "passive"))
      (node (ref "R5") (pin "1") (pinfunction "1_1") (pintype "passive"))
      (node (ref "R6") (pin "1") (pinfunction "1_1") (pintype "passive"))
      (node (ref "R7") (pin "1") (pinfunction "1_1") (pintype "passive"))
      (node (ref "S1") (pin "2") (pinfunction "0_2") (pintype "passive"))
      (node (ref "S2") (pin "2") (pinfunction "0_2") (pintype "passive"))
      (node (ref "S3") (pin "1") (pinfunction "0_1") (pintype "passive"))
      (node (ref "S3") (pin "3") (pinfunction "GND_3") (pintype "passive"))
      (node (ref "U1") (pin "17") (pinfunction "ThermalPad_17") (pintype "passive"))
      (node (ref "U1") (pin "8") (pinfunction "VSS_8") (pintype "passive"))
      (node (ref "U2") (pin "12") (pinfunction "GND_12") (pintype "passive"))
      (node (ref "U2") (pin "27") (pinfunction "GND_27") (pintype "passive"))
      (node (ref "U2") (pin "3") (pinfunction "GNDA_3") (pintype "passive"))
      (node (ref "U2") (pin "39") (pinfunction "GND_39") (pintype "passive"))
      (node (ref "U2") (pin "55") (pinfunction "GND_55") (pintype "passive"))
      (node (ref "U3") (pin "11") (pinfunction "PowerPAD_11") (pintype "passive"))
      (node (ref "U3") (pin "3") (pinfunction "PGND_3") (pintype "passive"))
      (node (ref "U3") (pin "9") (pinfunction "GND_9") (pintype "passive"))
    )
    (net (code "57") (name "Net-(D1-K)") (class "Default")
      (node (ref "D1") (pin "2") (pinfunction "K_2") (pintype "passive"))
      (node (ref "R28") (pin "2") (pinfunction "2_2") (pintype "passive"))
    )
    (net (code "58") (name "Net-(D2-K)") (class "Default")
      (node (ref "D2") (pin "2") (pinfunction "K_2") (pintype "passive"))
      (node (ref "R29") (pin "2") (pinfunction "2_2") (pintype "passive"))
    )
    (net (code "59") (name "Net-(J1-C1+)") (class "Default")
      (node (ref "C1") (pin "1") (pinfunction "1_1") (pintype "passive"))
      (node (ref "J1") (pin "8") (pinfunction "C1+_8") (pintype "passive"))
    )
    (net (code "60") (name "Net-(J1-C1-)") (class "Default")
      (node (ref "C1") (pin "2") (pinfunction "2_2") (pintype "passive"))
      (node (ref "J1") (pin "9") (pinfunction "C1-_9") (pintype "passive"))
    )
    (net (code "61") (name "Net-(J1-C2+)") (class "Default")
      (node (ref "C2") (pin "1") (pinfunction "1_1") (pintype "passive"))
      (node (ref "J1") (pin "7") (pinfunction "C2+_7") (pintype "passive"))
    )
    (net (code "62") (name "Net-(J1-C2-)") (class "Default")
      (node (ref "C2") (pin "2") (pinfunction "2_2") (pintype "passive"))
      (node (ref "J1") (pin "6") (pinfunction "C2-_6") (pintype "passive"))
    )
    (net (code "63") (name "Net-(J1-LED+)") (class "Default")
      (node (ref "J1") (pin "18") (pinfunction "LED+_18") (pintype "passive"))
      (node (ref "R1") (pin "2") (pinfunction "2_2") (pintype "passive"))
    )
    (net (code "64") (name "Net-(R12-Pad2)") (class "Default")
      (node (ref "R12") (pin "2") (pinfunction "2_2") (pintype "passive"))
      (node (ref "S3") (pin "2") (pinfunction "0_2") (pintype "passive"))
    )
    (net (code "65") (name "Net-(U1-ILIM)") (class "Default")
      (node (ref "R5") (pin "2") (pinfunction "2_2") (pintype "passive"))
      (node (ref "U1") (pin "12") (pinfunction "ILIM_12") (pintype "passive"))
    )
    (net (code "66") (name "Net-(U1-ISET)") (class "Default")
      (node (ref "R7") (pin "2") (pinfunction "2_2") (pintype "passive"))
      (node (ref "U1") (pin "16") (pinfunction "ISET_16") (pintype "passive"))
    )
    (net (code "67") (name "Net-(U1-TD{slash}ITERM)") (class "Default")
      (node (ref "R6") (pin "2") (pinfunction "2_2") (pintype "passive"))
      (node (ref "U1") (pin "15") (pinfunction "TD/ITERM_15") (pintype "passive"))
    )
    (net (code "68") (name "Net-(U1-TMR)") (class "Default")
      (node (ref "R4") (pin "2") (pinfunction "2_2") (pintype "passive"))
      (node (ref "U1") (pin "14") (pinfunction "TMR_14") (pintype "passive"))
    )
    (net (code "69") (name "Net-(U2B-GNDX)") (class "Default")
      (node (ref "C22") (pin "2") (pinfunction "2_2") (pintype "passive"))
      (node (ref "C23") (pin "2") (pinfunction "2_2") (pintype "passive"))
      (node (ref "U2") (pin "35") (pinfunction "GNDX_35") (pintype "passive"))
    )
    (net (code "70") (name "Net-(U2B-OSC0)") (class "Default")
      (node (ref "C15") (pin "1") (pinfunction "1_1") (pintype "passive"))
      (node (ref "U2") (pin "40") (pinfunction "OSC0_40") (pintype "passive"))
      (node (ref "Y1") (pin "2") (pinfunction "OSC2_2") (pintype "passive"))
    )
    (net (code "71") (name "Net-(U2B-OSC1)") (class "Default")
      (node (ref "C14") (pin "1") (pinfunction "1_1") (pintype "passive"))
      (node (ref "U2") (pin "41") (pinfunction "OSC1_41") (pintype "passive"))
      (node (ref "Y1") (pin "1") (pinfunction "OSC1_1") (pintype "passive"))
    )
    (net (code "72") (name "Net-(U2B-XOSC0)") (class "Default")
      (node (ref "C22") (pin "1") (pinfunction "1_1") (pintype "passive"))
      (node (ref "U2") (pin "34") (pinfunction "XOSC0_34") (pintype "passive"))
      (node (ref "Y2") (pin "1") (pinfunction "OSC1_1") (pintype "passive"))
    )
    (net (code "73") (name "Net-(U2B-XOSC1)") (class "Default")
      (node (ref "C23") (pin "1") (pinfunction "1_1") (pintype "passive"))
      (node (ref "U2") (pin "36") (pinfunction "XOSC1_36") (pintype "passive"))
      (node (ref "Y2") (pin "2") (pinfunction "OSC2_2") (pintype "passive"))
    )
    (net (code "74") (name "Net-(U3-L1)") (class "Default")
      (node (ref "L1") (pin "1") (pinfunction "1_1") (pintype "passive"))
      (node (ref "U3") (pin "4") (pinfunction "L1_4") (pintype "passive"))
    )
    (net (code "75") (name "Net-(U3-L2)") (class "Default")
      (node (ref "L1") (pin "2") (pinfunction "2_2") (pintype "passive"))
      (node (ref "U3") (pin "2") (pinfunction "L2_2") (pintype "passive"))
    )
    (net (code "76") (name "unconnected-(J2-DAT1-Pad8)") (class "Default")
      (node (ref "J2") (pin "8") (pinfunction "DAT1_8") (pintype "passive+no_connect"))
    )
    (net (code "77") (name "unconnected-(J2-DAT2-Pad1)") (class "Default")
      (node (ref "J2") (pin "1") (pinfunction "DAT2_1") (pintype "passive+no_connect"))
    )
    (net (code "78") (name "unconnected-(P4-NC-Pad1)") (class "Default")
      (node (ref "P4") (pin "1") (pinfunction "NC_1") (pintype "passive"))
    )
    (net (code "79") (name "unconnected-(P4-NC-Pad7)") (class "Default")
      (node (ref "P4") (pin "7") (pinfunction "NC_7") (pintype "passive"))
    )
    (net (code "80") (name "unconnected-(U2A-PA6-Pad23)") (class "Default")
      (node (ref "U2") (pin "23") (pinfunction "PA6_23") (pintype "passive"))
    )
    (net (code "81") (name "unconnected-(U2A-PA7-Pad24)") (class "Default")
      (node (ref "U2") (pin "24") (pinfunction "PA7_24") (pintype "passive"))
    )
    (net (code "82") (name "unconnected-(U2A-PE4-Pad59)") (class "Default")
      (node (ref "U2") (pin "59") (pinfunction "PE4_59") (pintype "passive"))
    )
    (net (code "83") (name "unconnected-(U2A-PF0-Pad28)") (class "Default")
      (node (ref "U2") (pin "28") (pinfunction "PF0_28") (pintype "passive"))
    )
  )
)
